# Teensy3_2_4IN_4OUTmcp4628.net
KiCad netlist of a schematic drawn in EAGLE
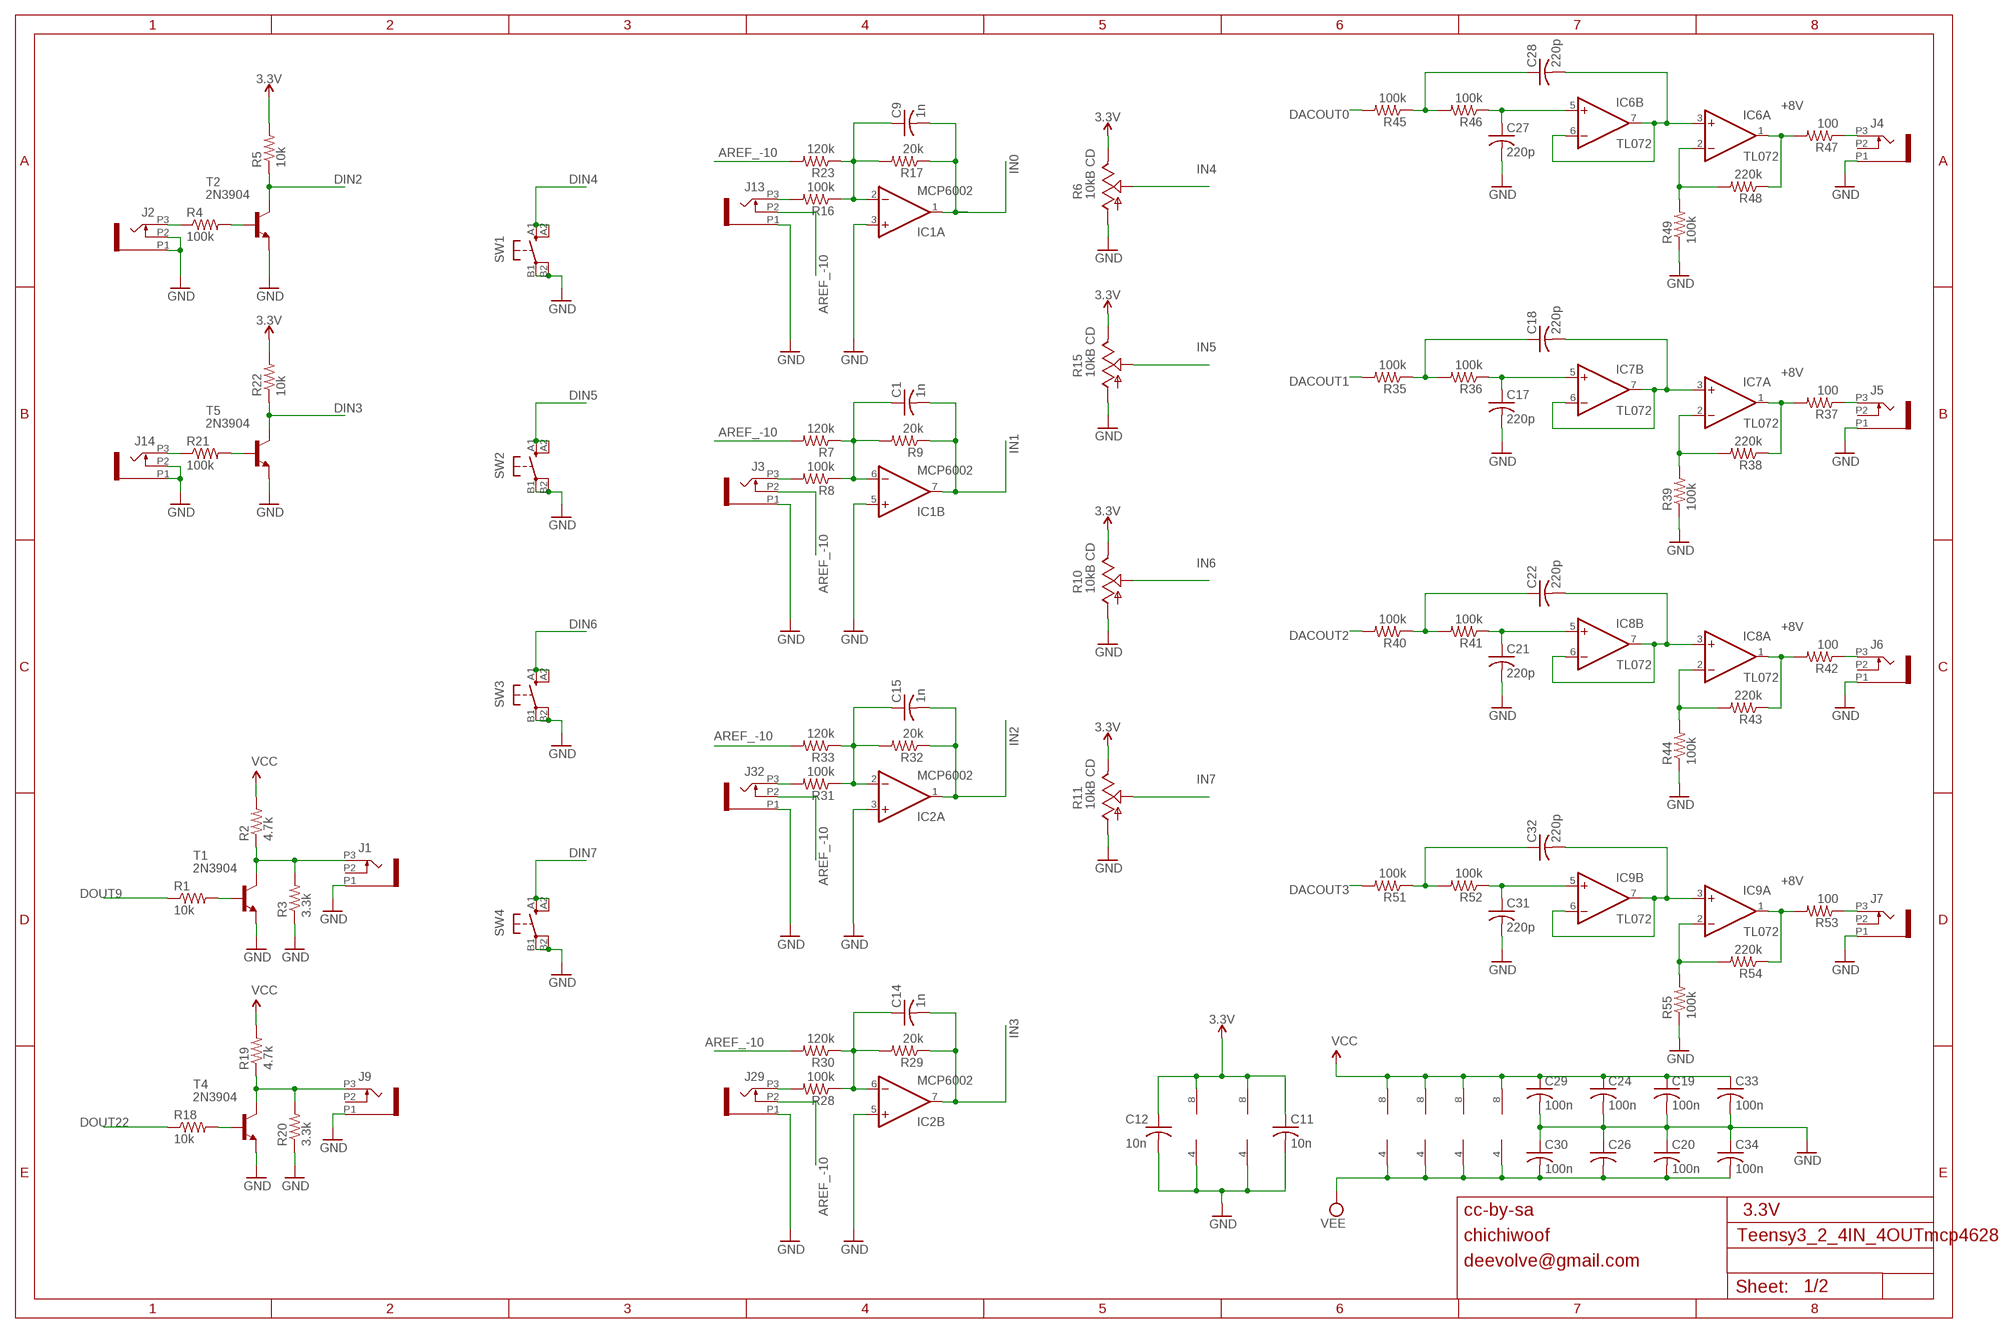
[diagram p0: schematic, sheet 1]
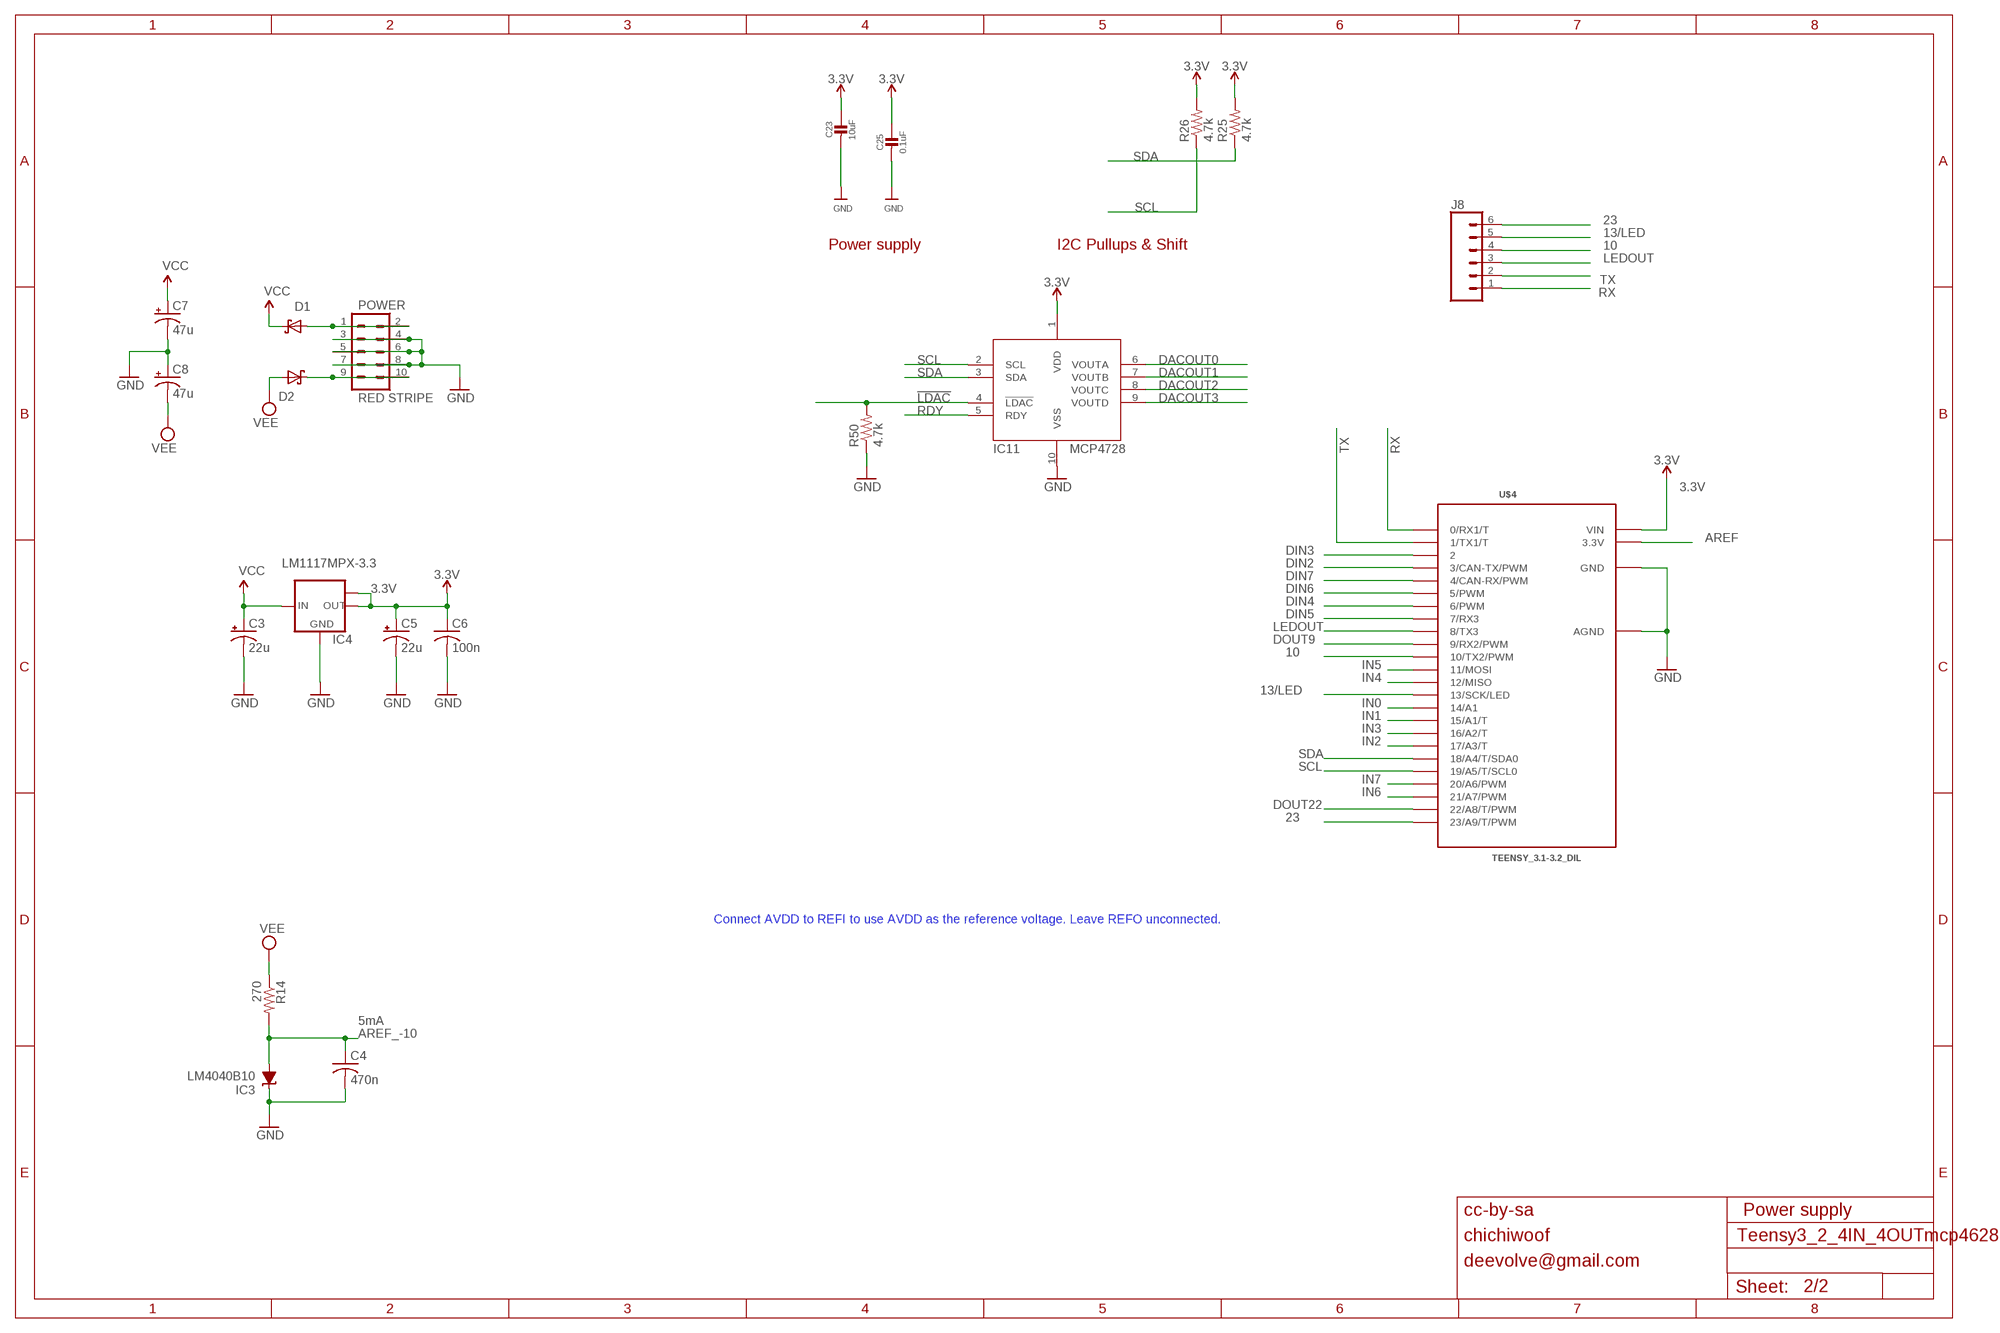
[diagram p1: schematic, sheet 2]

(export (version "E")
  (design (tool "Eeschema 10.0.6"))
  (components
    (comp (ref "C1")
      (value "1n")
      (footprint "eagle-import:C050-025X075")
      (libsource (lib "eagle-import") (part "C-US050-025X075"))
    )
    (comp (ref "C9")
      (value "1n")
      (footprint "eagle-import:C050-025X075")
      (libsource (lib "eagle-import") (part "C-US050-025X075"))
    )
    (comp (ref "C11")
      (value "10n")
      (footprint "eagle-import:C050-025X075")
      (libsource (lib "eagle-import") (part "C-US050-025X075"))
    )
    (comp (ref "C12")
      (value "10n")
      (footprint "eagle-import:C050-025X075")
      (libsource (lib "eagle-import") (part "C-US050-025X075"))
    )
    (comp (ref "C14")
      (value "1n")
      (footprint "eagle-import:C050-025X075")
      (libsource (lib "eagle-import") (part "C-US050-025X075"))
    )
    (comp (ref "C15")
      (value "1n")
      (footprint "eagle-import:C050-025X075")
      (libsource (lib "eagle-import") (part "C-US050-025X075"))
    )
    (comp (ref "C17")
      (value "220p")
      (footprint "eagle-import:C050-025X075")
      (libsource (lib "eagle-import") (part "C-US050-025X075"))
    )
    (comp (ref "C18")
      (value "220p")
      (footprint "eagle-import:C050-025X075")
      (libsource (lib "eagle-import") (part "C-US050-025X075"))
    )
    (comp (ref "C19")
      (value "100n")
      (footprint "eagle-import:C050-025X075")
      (libsource (lib "eagle-import") (part "C-US050-025X075"))
    )
    (comp (ref "C20")
      (value "100n")
      (footprint "eagle-import:C050-025X075")
      (libsource (lib "eagle-import") (part "C-US050-025X075"))
    )
    (comp (ref "C21")
      (value "220p")
      (footprint "eagle-import:C050-025X075")
      (libsource (lib "eagle-import") (part "C-US050-025X075"))
    )
    (comp (ref "C22")
      (value "220p")
      (footprint "eagle-import:C050-025X075")
      (libsource (lib "eagle-import") (part "C-US050-025X075"))
    )
    (comp (ref "C24")
      (value "100n")
      (footprint "eagle-import:C050-025X075")
      (libsource (lib "eagle-import") (part "C-US050-025X075"))
    )
    (comp (ref "C26")
      (value "100n")
      (footprint "eagle-import:C050-025X075")
      (libsource (lib "eagle-import") (part "C-US050-025X075"))
    )
    (comp (ref "C27")
      (value "220p")
      (footprint "eagle-import:C050-025X075")
      (libsource (lib "eagle-import") (part "C-US050-025X075"))
    )
    (comp (ref "C28")
      (value "220p")
      (footprint "eagle-import:C050-025X075")
      (libsource (lib "eagle-import") (part "C-US050-025X075"))
    )
    (comp (ref "C29")
      (value "100n")
      (footprint "eagle-import:C050-025X075")
      (libsource (lib "eagle-import") (part "C-US050-025X075"))
    )
    (comp (ref "C30")
      (value "100n")
      (footprint "eagle-import:C050-025X075")
      (libsource (lib "eagle-import") (part "C-US050-025X075"))
    )
    (comp (ref "C31")
      (value "220p")
      (footprint "eagle-import:C050-025X075")
      (libsource (lib "eagle-import") (part "C-US050-025X075"))
    )
    (comp (ref "C32")
      (value "220p")
      (footprint "eagle-import:C050-025X075")
      (libsource (lib "eagle-import") (part "C-US050-025X075"))
    )
    (comp (ref "C33")
      (value "100n")
      (footprint "eagle-import:C050-025X075")
      (libsource (lib "eagle-import") (part "C-US050-025X075"))
    )
    (comp (ref "C34")
      (value "100n")
      (footprint "eagle-import:C050-025X075")
      (libsource (lib "eagle-import") (part "C-US050-025X075"))
    )
    (comp (ref "IC1")
      (value "MCP6002")
      (footprint "eagle-import:SO08")
      (libsource (lib "eagle-import") (part "TL072D"))
    )
    (comp (ref "IC2")
      (value "MCP6002")
      (footprint "eagle-import:SO08")
      (libsource (lib "eagle-import") (part "TL072D"))
    )
    (comp (ref "IC6")
      (value "TL072")
      (footprint "eagle-import:SO08")
      (libsource (lib "eagle-import") (part "TL072D"))
    )
    (comp (ref "IC7")
      (value "TL072")
      (footprint "eagle-import:SO08")
      (libsource (lib "eagle-import") (part "TL072D"))
    )
    (comp (ref "IC8")
      (value "TL072")
      (footprint "eagle-import:SO08")
      (libsource (lib "eagle-import") (part "TL072D"))
    )
    (comp (ref "IC9")
      (value "TL072")
      (footprint "eagle-import:SO08")
      (libsource (lib "eagle-import") (part "TL072D"))
    )
    (comp (ref "J1")
      (value "PJ301_THONKICONN6")
      (footprint "eagle-import:WQP_PJ_301M6")
      (libsource (lib "eagle-import") (part "PJ301_THONKICONN6"))
    )
    (comp (ref "J2")
      (value "PJ301_THONKICONN6")
      (footprint "eagle-import:WQP_PJ_301M6")
      (libsource (lib "eagle-import") (part "PJ301_THONKICONN6"))
    )
    (comp (ref "J3")
      (value "PJ301_THONKICONN6")
      (footprint "eagle-import:WQP_PJ_301M6")
      (libsource (lib "eagle-import") (part "PJ301_THONKICONN6"))
    )
    (comp (ref "J4")
      (value "PJ301_THONKICONN6")
      (footprint "eagle-import:WQP_PJ_301M6")
      (libsource (lib "eagle-import") (part "PJ301_THONKICONN6"))
    )
    (comp (ref "J5")
      (value "PJ301_THONKICONN6")
      (footprint "eagle-import:WQP_PJ_301M6")
      (libsource (lib "eagle-import") (part "PJ301_THONKICONN6"))
    )
    (comp (ref "J6")
      (value "PJ301_THONKICONN6")
      (footprint "eagle-import:WQP_PJ_301M6")
      (libsource (lib "eagle-import") (part "PJ301_THONKICONN6"))
    )
    (comp (ref "J7")
      (value "PJ301_THONKICONN6")
      (footprint "eagle-import:WQP_PJ_301M6")
      (libsource (lib "eagle-import") (part "PJ301_THONKICONN6"))
    )
    (comp (ref "J9")
      (value "PJ301_THONKICONN6")
      (footprint "eagle-import:WQP_PJ_301M6")
      (libsource (lib "eagle-import") (part "PJ301_THONKICONN6"))
    )
    (comp (ref "J13")
      (value "PJ301_THONKICONN6")
      (footprint "eagle-import:WQP_PJ_301M6")
      (libsource (lib "eagle-import") (part "PJ301_THONKICONN6"))
    )
    (comp (ref "J14")
      (value "PJ301_THONKICONN6")
      (footprint "eagle-import:WQP_PJ_301M6")
      (libsource (lib "eagle-import") (part "PJ301_THONKICONN6"))
    )
    (comp (ref "J29")
      (value "PJ301_THONKICONN6")
      (footprint "eagle-import:WQP_PJ_301M6")
      (libsource (lib "eagle-import") (part "PJ301_THONKICONN6"))
    )
    (comp (ref "J32")
      (value "PJ301_THONKICONN6")
      (footprint "eagle-import:WQP_PJ_301M6")
      (libsource (lib "eagle-import") (part "PJ301_THONKICONN6"))
    )
    (comp (ref "R1")
      (value "10k")
      (footprint "eagle-import:0204_7")
      (libsource (lib "eagle-import") (part "R-US_0204/7"))
    )
    (comp (ref "R2")
      (value "4.7k")
      (footprint "eagle-import:0204_7")
      (libsource (lib "eagle-import") (part "R-US_0204/7"))
    )
    (comp (ref "R3")
      (value "3.3k")
      (footprint "eagle-import:0204_7")
      (libsource (lib "eagle-import") (part "R-US_0204/7"))
    )
    (comp (ref "R4")
      (value "100k")
      (footprint "eagle-import:0204_7")
      (libsource (lib "eagle-import") (part "R-US_0204/7"))
    )
    (comp (ref "R5")
      (value "10k")
      (footprint "eagle-import:0204_7")
      (libsource (lib "eagle-import") (part "R-US_0204/7"))
    )
    (comp (ref "R6")
      (value "10kB CD")
      (footprint "eagle-import:ALPS_POT_VERTICAL_PS")
      (libsource (lib "eagle-import") (part "POT_USVERTICAL_PS"))
    )
    (comp (ref "R7")
      (value "120k")
      (footprint "eagle-import:0204_7")
      (libsource (lib "eagle-import") (part "R-US_0204/7"))
    )
    (comp (ref "R8")
      (value "100k")
      (footprint "eagle-import:0204_7")
      (libsource (lib "eagle-import") (part "R-US_0204/7"))
    )
    (comp (ref "R9")
      (value "20k")
      (footprint "eagle-import:0204_7")
      (libsource (lib "eagle-import") (part "R-US_0204/7"))
    )
    (comp (ref "R10")
      (value "10kB CD")
      (footprint "eagle-import:ALPS_POT_VERTICAL_PS")
      (libsource (lib "eagle-import") (part "POT_USVERTICAL_PS"))
    )
    (comp (ref "R11")
      (value "10kB CD")
      (footprint "eagle-import:ALPS_POT_VERTICAL_PS")
      (libsource (lib "eagle-import") (part "POT_USVERTICAL_PS"))
    )
    (comp (ref "R15")
      (value "10kB CD")
      (footprint "eagle-import:ALPS_POT_VERTICAL_PS")
      (libsource (lib "eagle-import") (part "POT_USVERTICAL_PS"))
    )
    (comp (ref "R16")
      (value "100k")
      (footprint "eagle-import:0204_7")
      (libsource (lib "eagle-import") (part "R-US_0204/7"))
    )
    (comp (ref "R17")
      (value "20k")
      (footprint "eagle-import:0204_7")
      (libsource (lib "eagle-import") (part "R-US_0204/7"))
    )
    (comp (ref "R18")
      (value "10k")
      (footprint "eagle-import:0204_7")
      (libsource (lib "eagle-import") (part "R-US_0204/7"))
    )
    (comp (ref "R19")
      (value "4.7k")
      (footprint "eagle-import:0204_7")
      (libsource (lib "eagle-import") (part "R-US_0204/7"))
    )
    (comp (ref "R20")
      (value "3.3k")
      (footprint "eagle-import:0204_7")
      (libsource (lib "eagle-import") (part "R-US_0204/7"))
    )
    (comp (ref "R21")
      (value "100k")
      (footprint "eagle-import:0204_7")
      (libsource (lib "eagle-import") (part "R-US_0204/7"))
    )
    (comp (ref "R22")
      (value "10k")
      (footprint "eagle-import:0204_7")
      (libsource (lib "eagle-import") (part "R-US_0204/7"))
    )
    (comp (ref "R23")
      (value "120k")
      (footprint "eagle-import:0204_7")
      (libsource (lib "eagle-import") (part "R-US_0204/7"))
    )
    (comp (ref "R28")
      (value "100k")
      (footprint "eagle-import:0204_7")
      (libsource (lib "eagle-import") (part "R-US_0204/7"))
    )
    (comp (ref "R29")
      (value "20k")
      (footprint "eagle-import:0204_7")
      (libsource (lib "eagle-import") (part "R-US_0204/7"))
    )
    (comp (ref "R30")
      (value "120k")
      (footprint "eagle-import:0204_7")
      (libsource (lib "eagle-import") (part "R-US_0204/7"))
    )
    (comp (ref "R31")
      (value "100k")
      (footprint "eagle-import:0204_7")
      (libsource (lib "eagle-import") (part "R-US_0204/7"))
    )
    (comp (ref "R32")
      (value "20k")
      (footprint "eagle-import:0204_7")
      (libsource (lib "eagle-import") (part "R-US_0204/7"))
    )
    (comp (ref "R33")
      (value "120k")
      (footprint "eagle-import:0204_7")
      (libsource (lib "eagle-import") (part "R-US_0204/7"))
    )
    (comp (ref "R35")
      (value "100k")
      (footprint "eagle-import:0204_7")
      (libsource (lib "eagle-import") (part "R-US_0204/7"))
    )
    (comp (ref "R36")
      (value "100k")
      (footprint "eagle-import:0204_7")
      (libsource (lib "eagle-import") (part "R-US_0204/7"))
    )
    (comp (ref "R37")
      (value "100")
      (footprint "eagle-import:0204_7")
      (libsource (lib "eagle-import") (part "R-US_0204/7"))
    )
    (comp (ref "R38")
      (value "220k")
      (footprint "eagle-import:0204_7")
      (libsource (lib "eagle-import") (part "R-US_0204/7"))
    )
    (comp (ref "R39")
      (value "100k")
      (footprint "eagle-import:0204_7")
      (libsource (lib "eagle-import") (part "R-US_0204/7"))
    )
    (comp (ref "R40")
      (value "100k")
      (footprint "eagle-import:0204_7")
      (libsource (lib "eagle-import") (part "R-US_0204/7"))
    )
    (comp (ref "R41")
      (value "100k")
      (footprint "eagle-import:0204_7")
      (libsource (lib "eagle-import") (part "R-US_0204/7"))
    )
    (comp (ref "R42")
      (value "100")
      (footprint "eagle-import:0204_7")
      (libsource (lib "eagle-import") (part "R-US_0204/7"))
    )
    (comp (ref "R43")
      (value "220k")
      (footprint "eagle-import:0204_7")
      (libsource (lib "eagle-import") (part "R-US_0204/7"))
    )
    (comp (ref "R44")
      (value "100k")
      (footprint "eagle-import:0204_7")
      (libsource (lib "eagle-import") (part "R-US_0204/7"))
    )
    (comp (ref "R45")
      (value "100k")
      (footprint "eagle-import:0204_7")
      (libsource (lib "eagle-import") (part "R-US_0204/7"))
    )
    (comp (ref "R46")
      (value "100k")
      (footprint "eagle-import:0204_7")
      (libsource (lib "eagle-import") (part "R-US_0204/7"))
    )
    (comp (ref "R47")
      (value "100")
      (footprint "eagle-import:0204_7")
      (libsource (lib "eagle-import") (part "R-US_0204/7"))
    )
    (comp (ref "R48")
      (value "220k")
      (footprint "eagle-import:0204_7")
      (libsource (lib "eagle-import") (part "R-US_0204/7"))
    )
    (comp (ref "R49")
      (value "100k")
      (footprint "eagle-import:0204_7")
      (libsource (lib "eagle-import") (part "R-US_0204/7"))
    )
    (comp (ref "R51")
      (value "100k")
      (footprint "eagle-import:0204_7")
      (libsource (lib "eagle-import") (part "R-US_0204/7"))
    )
    (comp (ref "R52")
      (value "100k")
      (footprint "eagle-import:0204_7")
      (libsource (lib "eagle-import") (part "R-US_0204/7"))
    )
    (comp (ref "R53")
      (value "100")
      (footprint "eagle-import:0204_7")
      (libsource (lib "eagle-import") (part "R-US_0204/7"))
    )
    (comp (ref "R54")
      (value "220k")
      (footprint "eagle-import:0204_7")
      (libsource (lib "eagle-import") (part "R-US_0204/7"))
    )
    (comp (ref "R55")
      (value "100k")
      (footprint "eagle-import:0204_7")
      (libsource (lib "eagle-import") (part "R-US_0204/7"))
    )
    (comp (ref "SW1")
      (value "D6R")
      (footprint "eagle-import:D6R")
      (libsource (lib "eagle-import") (part "D6R"))
    )
    (comp (ref "SW2")
      (value "D6R")
      (footprint "eagle-import:D6R")
      (libsource (lib "eagle-import") (part "D6R"))
    )
    (comp (ref "SW3")
      (value "D6R")
      (footprint "eagle-import:D6R")
      (libsource (lib "eagle-import") (part "D6R"))
    )
    (comp (ref "SW4")
      (value "D6R")
      (footprint "eagle-import:D6R")
      (libsource (lib "eagle-import") (part "D6R"))
    )
    (comp (ref "T1")
      (value "2N3904")
      (footprint "eagle-import:TO92")
      (libsource (lib "eagle-import") (part "2N3904"))
    )
    (comp (ref "T2")
      (value "2N3904")
      (footprint "eagle-import:TO92")
      (libsource (lib "eagle-import") (part "2N3904"))
    )
    (comp (ref "T4")
      (value "2N3904")
      (footprint "eagle-import:TO92")
      (libsource (lib "eagle-import") (part "2N3904"))
    )
    (comp (ref "T5")
      (value "2N3904")
      (footprint "eagle-import:TO92")
      (libsource (lib "eagle-import") (part "2N3904"))
    )
    (comp (ref "C3")
      (value "22u")
      (footprint "eagle-import:E2,5-7")
      (libsource (lib "eagle-import") (part "CPOL-USE2.5-7"))
    )
    (comp (ref "C4")
      (value "470n")
      (footprint "eagle-import:C050-025X075")
      (libsource (lib "eagle-import") (part "C-US050-025X075"))
    )
    (comp (ref "C5")
      (value "22u")
      (footprint "eagle-import:E2,5-7")
      (libsource (lib "eagle-import") (part "CPOL-USE2.5-7"))
    )
    (comp (ref "C6")
      (value "100n")
      (footprint "eagle-import:C050-025X075")
      (libsource (lib "eagle-import") (part "C-US050-025X075"))
    )
    (comp (ref "C7")
      (value "47u")
      (footprint "eagle-import:E2,5-7")
      (libsource (lib "eagle-import") (part "CPOL-USE2.5-7"))
    )
    (comp (ref "C8")
      (value "47u")
      (footprint "eagle-import:E2,5-7")
      (libsource (lib "eagle-import") (part "CPOL-USE2.5-7"))
    )
    (comp (ref "C23")
      (value "10uF")
      (footprint "eagle-import:0805-NO")
      (libsource (lib "eagle-import") (part "CAP_CERAMIC0805-NOOUTLINE"))
    )
    (comp (ref "C25")
      (value "0.1uF")
      (footprint "eagle-import:0603-NO")
      (libsource (lib "eagle-import") (part "CAP_CERAMIC0603_NO"))
    )
    (comp (ref "D1")
      (value "1N5819")
      (footprint "eagle-import:DO41-10")
      (libsource (lib "eagle-import") (part "SCHOTTKY-DIODEDO41"))
    )
    (comp (ref "D2")
      (value "1N5819")
      (footprint "eagle-import:DO41-10")
      (libsource (lib "eagle-import") (part "SCHOTTKY-DIODEDO41"))
    )
    (comp (ref "IC3")
      (value "LM4040B10")
      (footprint "eagle-import:DBZ_R-PDSO-G3")
      (libsource (lib "eagle-import") (part "LM4041DBZB12"))
    )
    (comp (ref "IC4")
      (value "LM1117MPX-3.3")
      (footprint "eagle-import:SOT223")
      (libsource (lib "eagle-import") (part "LM1117MPX-3.3"))
    )
    (comp (ref "IC11")
      (value "MCP4728")
      (footprint "eagle-import:MSOP10")
      (libsource (lib "eagle-import") (part "MCP4728"))
    )
    (comp (ref "J8")
      (value "CONN_06SILK_FEMALE_PTH")
      (footprint "eagle-import:1X06")
      (libsource (lib "eagle-import") (part "CONN_06SILK_FEMALE_PTH"))
    )
    (comp (ref "POWER")
      (value "RED STRIPE")
      (footprint "eagle-import:AVR_ICSP")
      (libsource (lib "eagle-import") (part "M05X2PTH"))
    )
    (comp (ref "R14")
      (value "270")
      (footprint "eagle-import:0204_7")
      (libsource (lib "eagle-import") (part "R-US_0204/7"))
    )
    (comp (ref "R25")
      (value "4.7k")
      (footprint "eagle-import:0204_7")
      (libsource (lib "eagle-import") (part "R-US_0204/7"))
    )
    (comp (ref "R26")
      (value "4.7k")
      (footprint "eagle-import:0204_7")
      (libsource (lib "eagle-import") (part "R-US_0204/7"))
    )
    (comp (ref "R50")
      (value "4.7k")
      (footprint "eagle-import:0204_7")
      (libsource (lib "eagle-import") (part "R-US_0204/7"))
    )
    (comp (ref "U$4")
      (value "TEENSY_3.1-3.2_DIL")
      (footprint "eagle-import:TEENSY_3.0-3.2&LC_DIL")
      (libsource (lib "eagle-import") (part "TEENSY_3.1-3.2_DIL"))
    )
  )
  (nets
    (net (code "1") (name "3.3V") (class "Default")
      (node (ref "C11") (pin "1") (pinfunction "1_1") (pintype "passive"))
      (node (ref "C12") (pin "1") (pinfunction "1_1") (pintype "passive"))
      (node (ref "C23") (pin "1") (pinfunction "1_1") (pintype "passive"))
      (node (ref "C25") (pin "1") (pinfunction "1_1") (pintype "passive"))
      (node (ref "C5") (pin "+") (pinfunction "+_+") (pintype "passive"))
      (node (ref "C6") (pin "1") (pinfunction "1_1") (pintype "passive"))
      (node (ref "IC1") (pin "8") (pinfunction "V+_8") (pintype "power_in"))
      (node (ref "IC11") (pin "1") (pinfunction "VDD_1") (pintype "power_in"))
      (node (ref "IC2") (pin "8") (pinfunction "V+_8") (pintype "power_in"))
      (node (ref "IC4") (pin "2") (pinfunction "OUT_2") (pintype "passive"))
      (node (ref "IC4") (pin "TAB") (pinfunction "OUT1_TAB") (pintype "passive"))
      (node (ref "R10") (pin "P$1") (pinfunction "E_P$1") (pintype "passive"))
      (node (ref "R11") (pin "P$1") (pinfunction "E_P$1") (pintype "passive"))
      (node (ref "R15") (pin "P$1") (pinfunction "E_P$1") (pintype "passive"))
      (node (ref "R22") (pin "2") (pinfunction "2_2") (pintype "passive"))
      (node (ref "R25") (pin "2") (pinfunction "2_2") (pintype "passive"))
      (node (ref "R26") (pin "2") (pinfunction "2_2") (pintype "passive"))
      (node (ref "R5") (pin "2") (pinfunction "2_2") (pintype "passive"))
      (node (ref "R6") (pin "P$1") (pinfunction "E_P$1") (pintype "passive"))
      (node (ref "U$4") (pin "VIN") (pinfunction "VIN_VIN") (pintype "power_in"))
    )
    (net (code "2") (name "10") (class "Default")
      (node (ref "J8") (pin "4") (pinfunction "4_4") (pintype "passive"))
      (node (ref "U$4") (pin "10") (pinfunction "10/TX2/PWM_10") (pintype "bidirectional"))
    )
    (net (code "3") (name "13{slash}LED") (class "Default")
      (node (ref "J8") (pin "5") (pinfunction "5_5") (pintype "passive"))
      (node (ref "U$4") (pin "13") (pinfunction "13/SCK/LED_13") (pintype "bidirectional"))
    )
    (net (code "4") (name "23") (class "Default")
      (node (ref "J8") (pin "6") (pinfunction "6_6") (pintype "passive"))
      (node (ref "U$4") (pin "23/A9") (pinfunction "23/A9/T/PWM_23/A9") (pintype "bidirectional"))
    )
    (net (code "5") (name "AREF") (class "Default")
      (node (ref "U$4") (pin "3.3V") (pinfunction "3.3V_3.3V") (pintype "power_in"))
    )
    (net (code "6") (name "AREF_-10") (class "Default")
      (node (ref "C4") (pin "1") (pinfunction "1_1") (pintype "passive"))
      (node (ref "IC3") (pin "2") (pinfunction "A_2") (pintype "passive"))
      (node (ref "J13") (pin "P2") (pinfunction "2_P2") (pintype "passive"))
      (node (ref "J29") (pin "P2") (pinfunction "2_P2") (pintype "passive"))
      (node (ref "J3") (pin "P2") (pinfunction "2_P2") (pintype "passive"))
      (node (ref "J32") (pin "P2") (pinfunction "2_P2") (pintype "passive"))
      (node (ref "R14") (pin "2") (pinfunction "2_2") (pintype "passive"))
      (node (ref "R23") (pin "2") (pinfunction "2_2") (pintype "passive"))
      (node (ref "R30") (pin "2") (pinfunction "2_2") (pintype "passive"))
      (node (ref "R33") (pin "2") (pinfunction "2_2") (pintype "passive"))
      (node (ref "R7") (pin "2") (pinfunction "2_2") (pintype "passive"))
    )
    (net (code "7") (name "DACOUT0") (class "Default")
      (node (ref "IC11") (pin "6") (pinfunction "VOUTA_6") (pintype "output"))
      (node (ref "R45") (pin "2") (pinfunction "2_2") (pintype "passive"))
    )
    (net (code "8") (name "DACOUT1") (class "Default")
      (node (ref "IC11") (pin "7") (pinfunction "VOUTB_7") (pintype "output"))
      (node (ref "R35") (pin "2") (pinfunction "2_2") (pintype "passive"))
    )
    (net (code "9") (name "DACOUT2") (class "Default")
      (node (ref "IC11") (pin "8") (pinfunction "VOUTC_8") (pintype "output"))
      (node (ref "R40") (pin "2") (pinfunction "2_2") (pintype "passive"))
    )
    (net (code "10") (name "DACOUT3") (class "Default")
      (node (ref "IC11") (pin "9") (pinfunction "VOUTD_9") (pintype "output"))
      (node (ref "R51") (pin "2") (pinfunction "2_2") (pintype "passive"))
    )
    (net (code "11") (name "DIN2") (class "Default")
      (node (ref "R5") (pin "1") (pinfunction "1_1") (pintype "passive"))
      (node (ref "T2") (pin "1") (pinfunction "C_1") (pintype "passive"))
      (node (ref "U$4") (pin "3") (pinfunction "3/CAN-TX/PWM_3") (pintype "bidirectional"))
    )
    (net (code "12") (name "DIN3") (class "Default")
      (node (ref "R22") (pin "1") (pinfunction "1_1") (pintype "passive"))
      (node (ref "T5") (pin "1") (pinfunction "C_1") (pintype "passive"))
      (node (ref "U$4") (pin "2") (pinfunction "2_2") (pintype "bidirectional"))
    )
    (net (code "13") (name "DIN4") (class "Default")
      (node (ref "SW1") (pin "A1") (pinfunction "S_A1") (pintype "passive"))
      (node (ref "SW1") (pin "A2") (pinfunction "S1_A2") (pintype "passive"))
      (node (ref "U$4") (pin "6") (pinfunction "6/PWM_6") (pintype "bidirectional"))
    )
    (net (code "14") (name "DIN5") (class "Default")
      (node (ref "SW2") (pin "A1") (pinfunction "S_A1") (pintype "passive"))
      (node (ref "SW2") (pin "A2") (pinfunction "S1_A2") (pintype "passive"))
      (node (ref "U$4") (pin "7") (pinfunction "7/RX3_7") (pintype "bidirectional"))
    )
    (net (code "15") (name "DIN6") (class "Default")
      (node (ref "SW3") (pin "A1") (pinfunction "S_A1") (pintype "passive"))
      (node (ref "SW3") (pin "A2") (pinfunction "S1_A2") (pintype "passive"))
      (node (ref "U$4") (pin "5") (pinfunction "5/PWM_5") (pintype "bidirectional"))
    )
    (net (code "16") (name "DIN7") (class "Default")
      (node (ref "SW4") (pin "A1") (pinfunction "S_A1") (pintype "passive"))
      (node (ref "SW4") (pin "A2") (pinfunction "S1_A2") (pintype "passive"))
      (node (ref "U$4") (pin "4") (pinfunction "4/CAN-RX/PWM_4") (pintype "bidirectional"))
    )
    (net (code "17") (name "DOUT9") (class "Default")
      (node (ref "R1") (pin "1") (pinfunction "1_1") (pintype "passive"))
      (node (ref "U$4") (pin "9") (pinfunction "9/RX2/PWM_9") (pintype "bidirectional"))
    )
    (net (code "18") (name "DOUT22") (class "Default")
      (node (ref "R18") (pin "1") (pinfunction "1_1") (pintype "passive"))
      (node (ref "U$4") (pin "22/A8") (pinfunction "22/A8/T/PWM_22/A8") (pintype "bidirectional"))
    )
    (net (code "19") (name "GND") (class "Default")
      (node (ref "C11") (pin "2") (pinfunction "2_2") (pintype "passive"))
      (node (ref "C12") (pin "2") (pinfunction "2_2") (pintype "passive"))
      (node (ref "C17") (pin "2") (pinfunction "2_2") (pintype "passive"))
      (node (ref "C19") (pin "2") (pinfunction "2_2") (pintype "passive"))
      (node (ref "C20") (pin "1") (pinfunction "1_1") (pintype "passive"))
      (node (ref "C21") (pin "2") (pinfunction "2_2") (pintype "passive"))
      (node (ref "C23") (pin "2") (pinfunction "2_2") (pintype "passive"))
      (node (ref "C24") (pin "2") (pinfunction "2_2") (pintype "passive"))
      (node (ref "C25") (pin "2") (pinfunction "2_2") (pintype "passive"))
      (node (ref "C26") (pin "1") (pinfunction "1_1") (pintype "passive"))
      (node (ref "C27") (pin "2") (pinfunction "2_2") (pintype "passive"))
      (node (ref "C29") (pin "2") (pinfunction "2_2") (pintype "passive"))
      (node (ref "C3") (pin "-") (pinfunction "-_-") (pintype "passive"))
      (node (ref "C30") (pin "1") (pinfunction "1_1") (pintype "passive"))
      (node (ref "C31") (pin "2") (pinfunction "2_2") (pintype "passive"))
      (node (ref "C33") (pin "2") (pinfunction "2_2") (pintype "passive"))
      (node (ref "C34") (pin "1") (pinfunction "1_1") (pintype "passive"))
      (node (ref "C4") (pin "2") (pinfunction "2_2") (pintype "passive"))
      (node (ref "C5") (pin "-") (pinfunction "-_-") (pintype "passive"))
      (node (ref "C6") (pin "2") (pinfunction "2_2") (pintype "passive"))
      (node (ref "C7") (pin "-") (pinfunction "-_-") (pintype "passive"))
      (node (ref "C8") (pin "+") (pinfunction "+_+") (pintype "passive"))
      (node (ref "IC1") (pin "3") (pinfunction "+IN_3") (pintype "input"))
      (node (ref "IC1") (pin "4") (pinfunction "V-_4") (pintype "power_in"))
      (node (ref "IC1") (pin "5") (pinfunction "+IN_5") (pintype "input"))
      (node (ref "IC11") (pin "10") (pinfunction "VSS_10") (pintype "power_in"))
      (node (ref "IC2") (pin "3") (pinfunction "+IN_3") (pintype "input"))
      (node (ref "IC2") (pin "4") (pinfunction "V-_4") (pintype "power_in"))
      (node (ref "IC2") (pin "5") (pinfunction "+IN_5") (pintype "input"))
      (node (ref "IC3") (pin "1") (pinfunction "C_1") (pintype "passive"))
      (node (ref "IC4") (pin "1") (pinfunction "GND_1") (pintype "input"))
      (node (ref "J1") (pin "P1") (pinfunction "1_P1") (pintype "passive"))
      (node (ref "J13") (pin "P1") (pinfunction "1_P1") (pintype "passive"))
      (node (ref "J14") (pin "P1") (pinfunction "1_P1") (pintype "passive"))
      (node (ref "J14") (pin "P2") (pinfunction "2_P2") (pintype "passive"))
      (node (ref "J2") (pin "P1") (pinfunction "1_P1") (pintype "passive"))
      (node (ref "J2") (pin "P2") (pinfunction "2_P2") (pintype "passive"))
      (node (ref "J29") (pin "P1") (pinfunction "1_P1") (pintype "passive"))
      (node (ref "J3") (pin "P1") (pinfunction "1_P1") (pintype "passive"))
      (node (ref "J32") (pin "P1") (pinfunction "1_P1") (pintype "passive"))
      (node (ref "J4") (pin "P1") (pinfunction "1_P1") (pintype "passive"))
      (node (ref "J5") (pin "P1") (pinfunction "1_P1") (pintype "passive"))
      (node (ref "J6") (pin "P1") (pinfunction "1_P1") (pintype "passive"))
      (node (ref "J7") (pin "P1") (pinfunction "1_P1") (pintype "passive"))
      (node (ref "J9") (pin "P1") (pinfunction "1_P1") (pintype "passive"))
      (node (ref "POWER") (pin "3") (pinfunction "3_3") (pintype "passive"))
      (node (ref "POWER") (pin "4") (pinfunction "4_4") (pintype "passive"))
      (node (ref "POWER") (pin "5") (pinfunction "5_5") (pintype "passive"))
      (node (ref "POWER") (pin "6") (pinfunction "6_6") (pintype "passive"))
      (node (ref "POWER") (pin "7") (pinfunction "7_7") (pintype "passive"))
      (node (ref "POWER") (pin "8") (pinfunction "8_8") (pintype "passive"))
      (node (ref "R10") (pin "P$3") (pinfunction "A_P$3") (pintype "passive"))
      (node (ref "R11") (pin "P$3") (pinfunction "A_P$3") (pintype "passive"))
      (node (ref "R15") (pin "P$3") (pinfunction "A_P$3") (pintype "passive"))
      (node (ref "R20") (pin "1") (pinfunction "1_1") (pintype "passive"))
      (node (ref "R3") (pin "1") (pinfunction "1_1") (pintype "passive"))
      (node (ref "R39") (pin "1") (pinfunction "1_1") (pintype "passive"))
      (node (ref "R44") (pin "1") (pinfunction "1_1") (pintype "passive"))
      (node (ref "R49") (pin "1") (pinfunction "1_1") (pintype "passive"))
      (node (ref "R50") (pin "1") (pinfunction "1_1") (pintype "passive"))
      (node (ref "R55") (pin "1") (pinfunction "1_1") (pintype "passive"))
      (node (ref "R6") (pin "P$3") (pinfunction "A_P$3") (pintype "passive"))
      (node (ref "SW1") (pin "B1") (pinfunction "P_B1") (pintype "passive"))
      (node (ref "SW1") (pin "B2") (pinfunction "P1_B2") (pintype "passive"))
      (node (ref "SW2") (pin "B1") (pinfunction "P_B1") (pintype "passive"))
      (node (ref "SW2") (pin "B2") (pinfunction "P1_B2") (pintype "passive"))
      (node (ref "SW3") (pin "B1") (pinfunction "P_B1") (pintype "passive"))
      (node (ref "SW3") (pin "B2") (pinfunction "P1_B2") (pintype "passive"))
      (node (ref "SW4") (pin "B1") (pinfunction "P_B1") (pintype "passive"))
      (node (ref "SW4") (pin "B2") (pinfunction "P1_B2") (pintype "passive"))
      (node (ref "T1") (pin "3") (pinfunction "E_3") (pintype "passive"))
      (node (ref "T2") (pin "3") (pinfunction "E_3") (pintype "passive"))
      (node (ref "T4") (pin "3") (pinfunction "E_3") (pintype "passive"))
      (node (ref "T5") (pin "3") (pinfunction "E_3") (pintype "passive"))
      (node (ref "U$4") (pin "AGND") (pinfunction "AGND_AGND") (pintype "power_in"))
      (node (ref "U$4") (pin "GND") (pinfunction "GND_GND") (pintype "power_in"))
    )
    (net (code "20") (name "IN0") (class "Default")
      (node (ref "C9") (pin "2") (pinfunction "2_2") (pintype "passive"))
      (node (ref "IC1") (pin "1") (pinfunction "OUT_1") (pintype "output"))
      (node (ref "R17") (pin "1") (pinfunction "1_1") (pintype "passive"))
      (node (ref "U$4") (pin "14/A0") (pinfunction "14/A1_14/A0") (pintype "bidirectional"))
    )
    (net (code "21") (name "IN1") (class "Default")
      (node (ref "C1") (pin "2") (pinfunction "2_2") (pintype "passive"))
      (node (ref "IC1") (pin "7") (pinfunction "OUT_7") (pintype "output"))
      (node (ref "R9") (pin "1") (pinfunction "1_1") (pintype "passive"))
      (node (ref "U$4") (pin "15/A1") (pinfunction "15/A1/T_15/A1") (pintype "bidirectional"))
    )
    (net (code "22") (name "IN2") (class "Default")
      (node (ref "C15") (pin "2") (pinfunction "2_2") (pintype "passive"))
      (node (ref "IC2") (pin "1") (pinfunction "OUT_1") (pintype "output"))
      (node (ref "R32") (pin "1") (pinfunction "1_1") (pintype "passive"))
      (node (ref "U$4") (pin "17/A3") (pinfunction "17/A3/T_17/A3") (pintype "bidirectional"))
    )
    (net (code "23") (name "IN3") (class "Default")
      (node (ref "C14") (pin "2") (pinfunction "2_2") (pintype "passive"))
      (node (ref "IC2") (pin "7") (pinfunction "OUT_7") (pintype "output"))
      (node (ref "R29") (pin "1") (pinfunction "1_1") (pintype "passive"))
      (node (ref "U$4") (pin "16/A2") (pinfunction "16/A2/T_16/A2") (pintype "bidirectional"))
    )
    (net (code "24") (name "IN4") (class "Default")
      (node (ref "R6") (pin "P$2") (pinfunction "S_P$2") (pintype "passive"))
      (node (ref "U$4") (pin "12") (pinfunction "12/MISO_12") (pintype "bidirectional"))
    )
    (net (code "25") (name "IN5") (class "Default")
      (node (ref "R15") (pin "P$2") (pinfunction "S_P$2") (pintype "passive"))
      (node (ref "U$4") (pin "11") (pinfunction "11/MOSI_11") (pintype "bidirectional"))
    )
    (net (code "26") (name "IN6") (class "Default")
      (node (ref "R10") (pin "P$2") (pinfunction "S_P$2") (pintype "passive"))
      (node (ref "U$4") (pin "21/A7") (pinfunction "21/A7/PWM_21/A7") (pintype "bidirectional"))
    )
    (net (code "27") (name "IN7") (class "Default")
      (node (ref "R11") (pin "P$2") (pinfunction "S_P$2") (pintype "passive"))
      (node (ref "U$4") (pin "20/A6") (pinfunction "20/A6/PWM_20/A6") (pintype "bidirectional"))
    )
    (net (code "28") (name "LEDOUT") (class "Default")
      (node (ref "J8") (pin "3") (pinfunction "3_3") (pintype "passive"))
      (node (ref "U$4") (pin "8") (pinfunction "8/TX3_8") (pintype "bidirectional"))
    )
    (net (code "29") (name "Net-(C18-Pad1)") (class "Default")
      (node (ref "C18") (pin "1") (pinfunction "1_1") (pintype "passive"))
      (node (ref "R35") (pin "1") (pinfunction "1_1") (pintype "passive"))
      (node (ref "R36") (pin "2") (pinfunction "2_2") (pintype "passive"))
    )
    (net (code "30") (name "Net-(C22-Pad1)") (class "Default")
      (node (ref "C22") (pin "1") (pinfunction "1_1") (pintype "passive"))
      (node (ref "R40") (pin "1") (pinfunction "1_1") (pintype "passive"))
      (node (ref "R41") (pin "2") (pinfunction "2_2") (pintype "passive"))
    )
    (net (code "31") (name "Net-(C28-Pad1)") (class "Default")
      (node (ref "C28") (pin "1") (pinfunction "1_1") (pintype "passive"))
      (node (ref "R45") (pin "1") (pinfunction "1_1") (pintype "passive"))
      (node (ref "R46") (pin "2") (pinfunction "2_2") (pintype "passive"))
    )
    (net (code "32") (name "Net-(C32-Pad1)") (class "Default")
      (node (ref "C32") (pin "1") (pinfunction "1_1") (pintype "passive"))
      (node (ref "R51") (pin "1") (pinfunction "1_1") (pintype "passive"))
      (node (ref "R52") (pin "2") (pinfunction "2_2") (pintype "passive"))
    )
    (net (code "33") (name "Net-(D1-PadA)") (class "Default")
      (node (ref "D1") (pin "A") (pinfunction "A_A") (pintype "passive"))
      (node (ref "POWER") (pin "1") (pinfunction "1_1") (pintype "passive"))
      (node (ref "POWER") (pin "2") (pinfunction "2_2") (pintype "passive"))
    )
    (net (code "34") (name "Net-(D2-PadC)") (class "Default")
      (node (ref "D2") (pin "C") (pinfunction "C_C") (pintype "passive"))
      (node (ref "POWER") (pin "10") (pinfunction "10_10") (pintype "passive"))
      (node (ref "POWER") (pin "9") (pinfunction "9_9") (pintype "passive"))
    )
    (net (code "35") (name "Net-(IC1A--IN)") (class "Default")
      (node (ref "C9") (pin "1") (pinfunction "1_1") (pintype "passive"))
      (node (ref "IC1") (pin "2") (pinfunction "-IN_2") (pintype "input"))
      (node (ref "R16") (pin "1") (pinfunction "1_1") (pintype "passive"))
      (node (ref "R17") (pin "2") (pinfunction "2_2") (pintype "passive"))
      (node (ref "R23") (pin "1") (pinfunction "1_1") (pintype "passive"))
    )
    (net (code "36") (name "Net-(IC1B--IN)") (class "Default")
      (node (ref "C1") (pin "1") (pinfunction "1_1") (pintype "passive"))
      (node (ref "IC1") (pin "6") (pinfunction "-IN_6") (pintype "input"))
      (node (ref "R7") (pin "1") (pinfunction "1_1") (pintype "passive"))
      (node (ref "R8") (pin "1") (pinfunction "1_1") (pintype "passive"))
      (node (ref "R9") (pin "2") (pinfunction "2_2") (pintype "passive"))
    )
    (net (code "37") (name "Net-(IC2A--IN)") (class "Default")
      (node (ref "C15") (pin "1") (pinfunction "1_1") (pintype "passive"))
      (node (ref "IC2") (pin "2") (pinfunction "-IN_2") (pintype "input"))
      (node (ref "R31") (pin "1") (pinfunction "1_1") (pintype "passive"))
      (node (ref "R32") (pin "2") (pinfunction "2_2") (pintype "passive"))
      (node (ref "R33") (pin "1") (pinfunction "1_1") (pintype "passive"))
    )
    (net (code "38") (name "Net-(IC2B--IN)") (class "Default")
      (node (ref "C14") (pin "1") (pinfunction "1_1") (pintype "passive"))
      (node (ref "IC2") (pin "6") (pinfunction "-IN_6") (pintype "input"))
      (node (ref "R28") (pin "1") (pinfunction "1_1") (pintype "passive"))
      (node (ref "R29") (pin "2") (pinfunction "2_2") (pintype "passive"))
      (node (ref "R30") (pin "1") (pinfunction "1_1") (pintype "passive"))
    )
    (net (code "39") (name "Net-(IC6A-+IN)") (class "Default")
      (node (ref "C28") (pin "2") (pinfunction "2_2") (pintype "passive"))
      (node (ref "IC6") (pin "3") (pinfunction "+IN_3") (pintype "input"))
      (node (ref "IC6") (pin "6") (pinfunction "-IN_6") (pintype "input"))
      (node (ref "IC6") (pin "7") (pinfunction "OUT_7") (pintype "output"))
    )
    (net (code "40") (name "Net-(IC6A--IN)") (class "Default")
      (node (ref "IC6") (pin "2") (pinfunction "-IN_2") (pintype "input"))
      (node (ref "R48") (pin "2") (pinfunction "2_2") (pintype "passive"))
      (node (ref "R49") (pin "2") (pinfunction "2_2") (pintype "passive"))
    )
    (net (code "41") (name "Net-(IC6A-OUT)") (class "Default")
      (node (ref "IC6") (pin "1") (pinfunction "OUT_1") (pintype "output"))
      (node (ref "R47") (pin "2") (pinfunction "2_2") (pintype "passive"))
      (node (ref "R48") (pin "1") (pinfunction "1_1") (pintype "passive"))
    )
    (net (code "42") (name "Net-(IC6B-+IN)") (class "Default")
      (node (ref "C27") (pin "1") (pinfunction "1_1") (pintype "passive"))
      (node (ref "IC6") (pin "5") (pinfunction "+IN_5") (pintype "input"))
      (node (ref "R46") (pin "1") (pinfunction "1_1") (pintype "passive"))
    )
    (net (code "43") (name "Net-(IC7A-+IN)") (class "Default")
      (node (ref "C18") (pin "2") (pinfunction "2_2") (pintype "passive"))
      (node (ref "IC7") (pin "3") (pinfunction "+IN_3") (pintype "input"))
      (node (ref "IC7") (pin "6") (pinfunction "-IN_6") (pintype "input"))
      (node (ref "IC7") (pin "7") (pinfunction "OUT_7") (pintype "output"))
    )
    (net (code "44") (name "Net-(IC7A--IN)") (class "Default")
      (node (ref "IC7") (pin "2") (pinfunction "-IN_2") (pintype "input"))
      (node (ref "R38") (pin "2") (pinfunction "2_2") (pintype "passive"))
      (node (ref "R39") (pin "2") (pinfunction "2_2") (pintype "passive"))
    )
    (net (code "45") (name "Net-(IC7A-OUT)") (class "Default")
      (node (ref "IC7") (pin "1") (pinfunction "OUT_1") (pintype "output"))
      (node (ref "R37") (pin "2") (pinfunction "2_2") (pintype "passive"))
      (node (ref "R38") (pin "1") (pinfunction "1_1") (pintype "passive"))
    )
    (net (code "46") (name "Net-(IC7B-+IN)") (class "Default")
      (node (ref "C17") (pin "1") (pinfunction "1_1") (pintype "passive"))
      (node (ref "IC7") (pin "5") (pinfunction "+IN_5") (pintype "input"))
      (node (ref "R36") (pin "1") (pinfunction "1_1") (pintype "passive"))
    )
    (net (code "47") (name "Net-(IC8A-+IN)") (class "Default")
      (node (ref "C22") (pin "2") (pinfunction "2_2") (pintype "passive"))
      (node (ref "IC8") (pin "3") (pinfunction "+IN_3") (pintype "input"))
      (node (ref "IC8") (pin "6") (pinfunction "-IN_6") (pintype "input"))
      (node (ref "IC8") (pin "7") (pinfunction "OUT_7") (pintype "output"))
    )
    (net (code "48") (name "Net-(IC8A--IN)") (class "Default")
      (node (ref "IC8") (pin "2") (pinfunction "-IN_2") (pintype "input"))
      (node (ref "R43") (pin "2") (pinfunction "2_2") (pintype "passive"))
      (node (ref "R44") (pin "2") (pinfunction "2_2") (pintype "passive"))
    )
    (net (code "49") (name "Net-(IC8A-OUT)") (class "Default")
      (node (ref "IC8") (pin "1") (pinfunction "OUT_1") (pintype "output"))
      (node (ref "R42") (pin "2") (pinfunction "2_2") (pintype "passive"))
      (node (ref "R43") (pin "1") (pinfunction "1_1") (pintype "passive"))
    )
    (net (code "50") (name "Net-(IC8B-+IN)") (class "Default")
      (node (ref "C21") (pin "1") (pinfunction "1_1") (pintype "passive"))
      (node (ref "IC8") (pin "5") (pinfunction "+IN_5") (pintype "input"))
      (node (ref "R41") (pin "1") (pinfunction "1_1") (pintype "passive"))
    )
    (net (code "51") (name "Net-(IC9A-+IN)") (class "Default")
      (node (ref "C32") (pin "2") (pinfunction "2_2") (pintype "passive"))
      (node (ref "IC9") (pin "3") (pinfunction "+IN_3") (pintype "input"))
      (node (ref "IC9") (pin "6") (pinfunction "-IN_6") (pintype "input"))
      (node (ref "IC9") (pin "7") (pinfunction "OUT_7") (pintype "output"))
    )
    (net (code "52") (name "Net-(IC9A--IN)") (class "Default")
      (node (ref "IC9") (pin "2") (pinfunction "-IN_2") (pintype "input"))
      (node (ref "R54") (pin "2") (pinfunction "2_2") (pintype "passive"))
      (node (ref "R55") (pin "2") (pinfunction "2_2") (pintype "passive"))
    )
    (net (code "53") (name "Net-(IC9A-OUT)") (class "Default")
      (node (ref "IC9") (pin "1") (pinfunction "OUT_1") (pintype "output"))
      (node (ref "R53") (pin "2") (pinfunction "2_2") (pintype "passive"))
      (node (ref "R54") (pin "1") (pinfunction "1_1") (pintype "passive"))
    )
    (net (code "54") (name "Net-(IC9B-+IN)") (class "Default")
      (node (ref "C31") (pin "1") (pinfunction "1_1") (pintype "passive"))
      (node (ref "IC9") (pin "5") (pinfunction "+IN_5") (pintype "input"))
      (node (ref "R52") (pin "1") (pinfunction "1_1") (pintype "passive"))
    )
    (net (code "55") (name "Net-(J1-3)") (class "Default")
      (node (ref "J1") (pin "P3") (pinfunction "3_P3") (pintype "passive"))
      (node (ref "R2") (pin "1") (pinfunction "1_1") (pintype "passive"))
      (node (ref "R3") (pin "2") (pinfunction "2_2") (pintype "passive"))
      (node (ref "T1") (pin "1") (pinfunction "C_1") (pintype "passive"))
    )
    (net (code "56") (name "Net-(J2-3)") (class "Default")
      (node (ref "J2") (pin "P3") (pinfunction "3_P3") (pintype "passive"))
      (node (ref "R4") (pin "1") (pinfunction "1_1") (pintype "passive"))
    )
    (net (code "57") (name "Net-(J3-3)") (class "Default")
      (node (ref "J3") (pin "P3") (pinfunction "3_P3") (pintype "passive"))
      (node (ref "R8") (pin "2") (pinfunction "2_2") (pintype "passive"))
    )
    (net (code "58") (name "Net-(J4-3)") (class "Default")
      (node (ref "J4") (pin "P3") (pinfunction "3_P3") (pintype "passive"))
      (node (ref "R47") (pin "1") (pinfunction "1_1") (pintype "passive"))
    )
    (net (code "59") (name "Net-(J5-3)") (class "Default")
      (node (ref "J5") (pin "P3") (pinfunction "3_P3") (pintype "passive"))
      (node (ref "R37") (pin "1") (pinfunction "1_1") (pintype "passive"))
    )
    (net (code "60") (name "Net-(J6-3)") (class "Default")
      (node (ref "J6") (pin "P3") (pinfunction "3_P3") (pintype "passive"))
      (node (ref "R42") (pin "1") (pinfunction "1_1") (pintype "passive"))
    )
    (net (code "61") (name "Net-(J7-3)") (class "Default")
      (node (ref "J7") (pin "P3") (pinfunction "3_P3") (pintype "passive"))
      (node (ref "R53") (pin "1") (pinfunction "1_1") (pintype "passive"))
    )
    (net (code "62") (name "Net-(J9-3)") (class "Default")
      (node (ref "J9") (pin "P3") (pinfunction "3_P3") (pintype "passive"))
      (node (ref "R19") (pin "1") (pinfunction "1_1") (pintype "passive"))
      (node (ref "R20") (pin "2") (pinfunction "2_2") (pintype "passive"))
      (node (ref "T4") (pin "1") (pinfunction "C_1") (pintype "passive"))
    )
    (net (code "63") (name "Net-(J13-3)") (class "Default")
      (node (ref "J13") (pin "P3") (pinfunction "3_P3") (pintype "passive"))
      (node (ref "R16") (pin "2") (pinfunction "2_2") (pintype "passive"))
    )
    (net (code "64") (name "Net-(J14-3)") (class "Default")
      (node (ref "J14") (pin "P3") (pinfunction "3_P3") (pintype "passive"))
      (node (ref "R21") (pin "1") (pinfunction "1_1") (pintype "passive"))
    )
    (net (code "65") (name "Net-(J29-3)") (class "Default")
      (node (ref "J29") (pin "P3") (pinfunction "3_P3") (pintype "passive"))
      (node (ref "R28") (pin "2") (pinfunction "2_2") (pintype "passive"))
    )
    (net (code "66") (name "Net-(J32-3)") (class "Default")
      (node (ref "J32") (pin "P3") (pinfunction "3_P3") (pintype "passive"))
      (node (ref "R31") (pin "2") (pinfunction "2_2") (pintype "passive"))
    )
    (net (code "67") (name "Net-(T1-B)") (class "Default")
      (node (ref "R1") (pin "2") (pinfunction "2_2") (pintype "passive"))
      (node (ref "T1") (pin "2") (pinfunction "B_2") (pintype "passive"))
    )
    (net (code "68") (name "Net-(T2-B)") (class "Default")
      (node (ref "R4") (pin "2") (pinfunction "2_2") (pintype "passive"))
      (node (ref "T2") (pin "2") (pinfunction "B_2") (pintype "passive"))
    )
    (net (code "69") (name "Net-(T4-B)") (class "Default")
      (node (ref "R18") (pin "2") (pinfunction "2_2") (pintype "passive"))
      (node (ref "T4") (pin "2") (pinfunction "B_2") (pintype "passive"))
    )
    (net (code "70") (name "Net-(T5-B)") (class "Default")
      (node (ref "R21") (pin "2") (pinfunction "2_2") (pintype "passive"))
      (node (ref "T5") (pin "2") (pinfunction "B_2") (pintype "passive"))
    )
    (net (code "71") (name "RDY") (class "Default")
      (node (ref "IC11") (pin "5") (pinfunction "RDY_5") (pintype "output"))
    )
    (net (code "72") (name "RX") (class "Default")
      (node (ref "J8") (pin "1") (pinfunction "1_1") (pintype "passive"))
      (node (ref "U$4") (pin "0") (pinfunction "0/RX1/T_0") (pintype "bidirectional"))
    )
    (net (code "73") (name "SCL") (class "Default")
      (node (ref "IC11") (pin "2") (pinfunction "SCL_2") (pintype "bidirectional"))
      (node (ref "R26") (pin "1") (pinfunction "1_1") (pintype "passive"))
      (node (ref "U$4") (pin "19/A5") (pinfunction "19/A5/T/SCL0_19/A5") (pintype "bidirectional"))
    )
    (net (code "74") (name "SDA") (class "Default")
      (node (ref "IC11") (pin "3") (pinfunction "SDA_3") (pintype "bidirectional"))
      (node (ref "R25") (pin "1") (pinfunction "1_1") (pintype "passive"))
      (node (ref "U$4") (pin "18/A4") (pinfunction "18/A4/T/SDA0_18/A4") (pintype "bidirectional"))
    )
    (net (code "75") (name "TX") (class "Default")
      (node (ref "J8") (pin "2") (pinfunction "2_2") (pintype "passive"))
      (node (ref "U$4") (pin "1") (pinfunction "1/TX1/T_1") (pintype "bidirectional"))
    )
    (net (code "76") (name "VCC") (class "Default")
      (node (ref "C19") (pin "1") (pinfunction "1_1") (pintype "passive"))
      (node (ref "C24") (pin "1") (pinfunction "1_1") (pintype "passive"))
      (node (ref "C29") (pin "1") (pinfunction "1_1") (pintype "passive"))
      (node (ref "C3") (pin "+") (pinfunction "+_+") (pintype "passive"))
      (node (ref "C33") (pin "1") (pinfunction "1_1") (pintype "passive"))
      (node (ref "C7") (pin "+") (pinfunction "+_+") (pintype "passive"))
      (node (ref "D1") (pin "C") (pinfunction "C_C") (pintype "passive"))
      (node (ref "IC4") (pin "3") (pinfunction "IN_3") (pintype "input"))
      (node (ref "IC6") (pin "8") (pinfunction "V+_8") (pintype "power_in"))
      (node (ref "IC7") (pin "8") (pinfunction "V+_8") (pintype "power_in"))
      (node (ref "IC8") (pin "8") (pinfunction "V+_8") (pintype "power_in"))
      (node (ref "IC9") (pin "8") (pinfunction "V+_8") (pintype "power_in"))
      (node (ref "R19") (pin "2") (pinfunction "2_2") (pintype "passive"))
      (node (ref "R2") (pin "2") (pinfunction "2_2") (pintype "passive"))
    )
    (net (code "77") (name "VEE") (class "Default")
      (node (ref "C20") (pin "2") (pinfunction "2_2") (pintype "passive"))
      (node (ref "C26") (pin "2") (pinfunction "2_2") (pintype "passive"))
      (node (ref "C30") (pin "2") (pinfunction "2_2") (pintype "passive"))
      (node (ref "C34") (pin "2") (pinfunction "2_2") (pintype "passive"))
      (node (ref "C8") (pin "-") (pinfunction "-_-") (pintype "passive"))
      (node (ref "D2") (pin "A") (pinfunction "A_A") (pintype "passive"))
      (node (ref "IC6") (pin "4") (pinfunction "V-_4") (pintype "power_in"))
      (node (ref "IC7") (pin "4") (pinfunction "V-_4") (pintype "power_in"))
      (node (ref "IC8") (pin "4") (pinfunction "V-_4") (pintype "power_in"))
      (node (ref "IC9") (pin "4") (pinfunction "V-_4") (pintype "power_in"))
      (node (ref "R14") (pin "1") (pinfunction "1_1") (pintype "passive"))
    )
    (net (code "78") (name "unconnected-(J1-2-PadP2)") (class "Default")
      (node (ref "J1") (pin "P2") (pinfunction "2_P2") (pintype "passive"))
    )
    (net (code "79") (name "unconnected-(J4-2-PadP2)") (class "Default")
      (node (ref "J4") (pin "P2") (pinfunction "2_P2") (pintype "passive"))
    )
    (net (code "80") (name "unconnected-(J5-2-PadP2)") (class "Default")
      (node (ref "J5") (pin "P2") (pinfunction "2_P2") (pintype "passive"))
    )
    (net (code "81") (name "unconnected-(J6-2-PadP2)") (class "Default")
      (node (ref "J6") (pin "P2") (pinfunction "2_P2") (pintype "passive"))
    )
    (net (code "82") (name "unconnected-(J7-2-PadP2)") (class "Default")
      (node (ref "J7") (pin "P2") (pinfunction "2_P2") (pintype "passive"))
    )
    (net (code "83") (name "unconnected-(J9-2-PadP2)") (class "Default")
      (node (ref "J9") (pin "P2") (pinfunction "2_P2") (pintype "passive"))
    )
    (net (code "84") (name "~{LDAC}") (class "Default")
      (node (ref "IC11") (pin "4") (pinfunction "~{LDAC}_4") (pintype "input"))
      (node (ref "R50") (pin "2") (pinfunction "2_2") (pintype "passive"))
    )
  )
)
